# LTE_GPS.net
KiCad netlist of a schematic drawn in Altium Designer
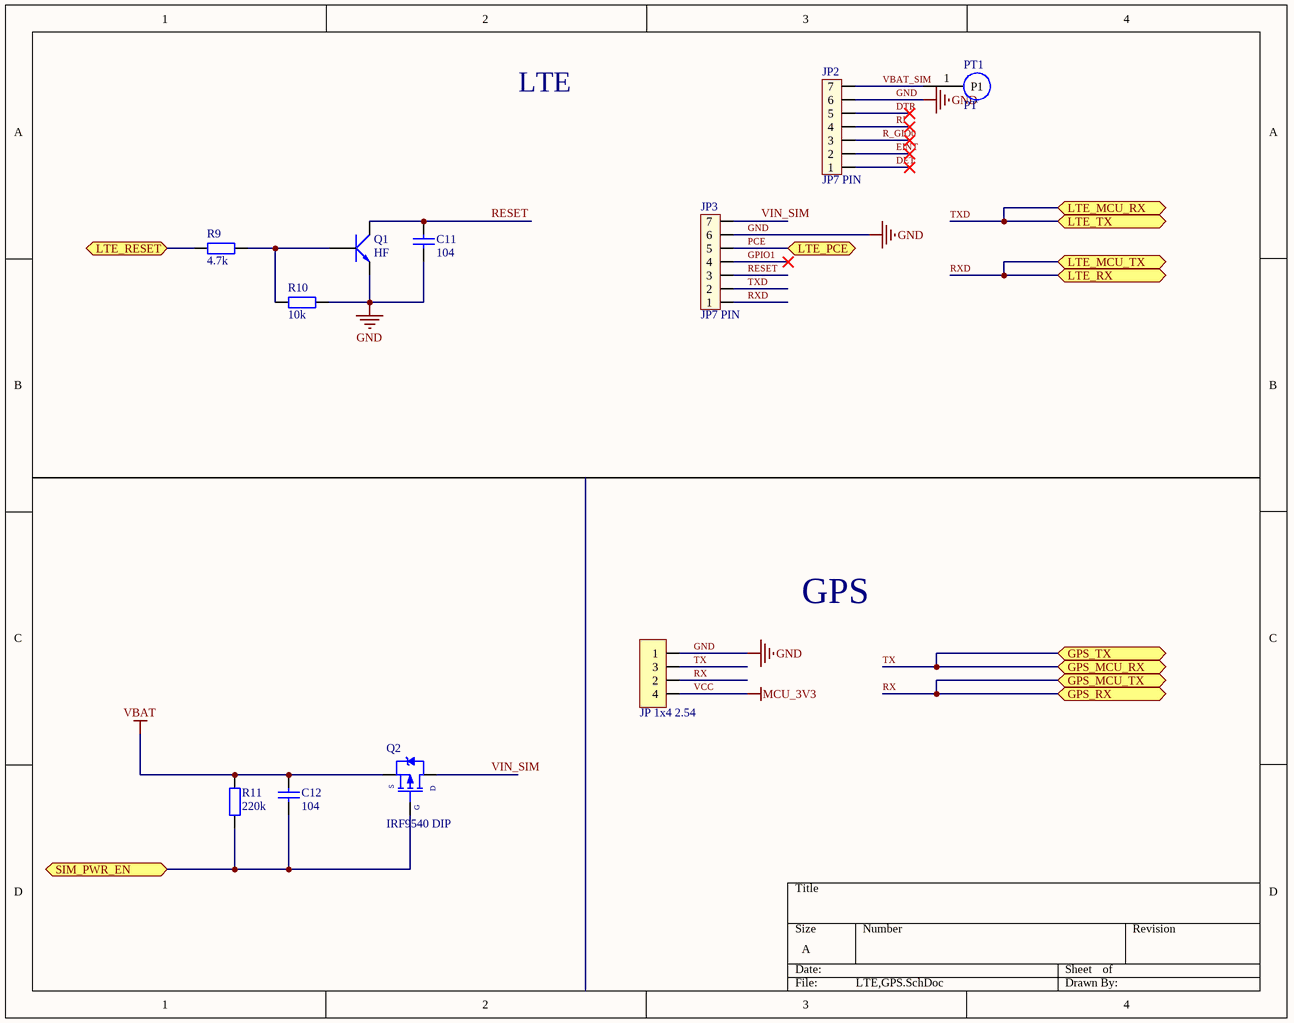
[diagram p0: LTE,GPS.SchDoc]

(export (version "E")
  (design (tool "Eeschema 10.0.6"))
  (components
    (comp (ref "C11")
      (value "104")
      (footprint "tu 0805")
      (description "Dán")
      (libsource (lib "Altium_Lib_by_KhueNguyenCreator") (part "Tu 0805 104 50V 10%"))
    )
    (comp (ref "C12")
      (value "104")
      (footprint "tu 0805")
      (description "Dán")
      (libsource (lib "Altium_Lib_by_KhueNguyenCreator") (part "Tu 0805 104 50V 10%"))
    )
    (comp (ref "JP2") (value "JP7 PIN") (footprint "JP7") (libsource (lib "syhaunguyen") (part "JP7")))
    (comp (ref "JP3") (value "JP7 PIN") (footprint "JP7") (libsource (lib "syhaunguyen") (part "JP7")))
    (comp (ref "JP4")
      (value "JP 1x4 2.54")
      (footprint "JP 1x4 DC")
      (description "Cắm")
      (libsource (lib "Altium_Lib_by_KhueNguyenCreator") (part "JP 1x4 2.54 Duc Cong"))
    )
    (comp (ref "PT1") (value "PT") (footprint "Test pont") (libsource (lib "Test pont") (part "test pont")))
    (comp (ref "Q1")
      (value "HF")
      (footprint "SOT23")
      (description "NPN transistor")
      (libsource (lib "Altium_Lib_by_KhueNguyenCreator") (part "C1815 HF SMD"))
    )
    (comp (ref "Q2")
      (value "IRF9540 DIP")
      (footprint "DPAK254P1511X469-3N")
      (description "P-Channel Power MOSFET")
      (fields (field (name "PUBLISHER") "Altium Limited"))
      (libsource (lib "Altium_Lib_by_KhueNguyenCreator") (part "IRF9540 DIP"))
    )
    (comp (ref "R9")
      (value "4.7k")
      (footprint "tro smd 0805")
      (description "Dán")
      (libsource (lib "Altium_Lib_by_KhueNguyenCreator") (part "Tro 0805 5% 4.7k"))
    )
    (comp (ref "R10")
      (value "10k")
      (footprint "tro smd 0805")
      (description "Dán")
      (libsource (lib "Altium_Lib_by_KhueNguyenCreator") (part "Tro 0805 5% 10k"))
    )
    (comp (ref "R11")
      (value "220k")
      (footprint "tro smd 0805")
      (description "Dán")
      (libsource (lib "Altium_Lib_by_KhueNguyenCreator") (part "Tro 0805 5% 220k"))
    )
  )
  (nets
    (net (code "1") (name "/DET") (class "Default")
      (node (ref "JP2") (pin "1") (pinfunction "1_1") (pintype "passive+no_connect"))
    )
    (net (code "2") (name "/DTR") (class "Default")
      (node (ref "JP2") (pin "5") (pinfunction "5_5") (pintype "passive+no_connect"))
    )
    (net (code "3") (name "/EINT") (class "Default")
      (node (ref "JP2") (pin "2") (pinfunction "2_2") (pintype "passive+no_connect"))
    )
    (net (code "4") (name "/GPIO1") (class "Default")
      (node (ref "JP3") (pin "4") (pinfunction "4_4") (pintype "passive+no_connect"))
    )
    (net (code "5") (name "/LTE_RESET") (class "Default")
      (node (ref "R9") (pin "1") (pinfunction "1_1") (pintype "passive"))
    )
    (net (code "6") (name "/PCE") (class "Default")
      (node (ref "JP3") (pin "5") (pinfunction "5_5") (pintype "passive"))
    )
    (net (code "7") (name "/RESET") (class "Default")
      (node (ref "C11") (pin "2") (pinfunction "2_2") (pintype "passive"))
      (node (ref "JP3") (pin "3") (pinfunction "3_3") (pintype "passive"))
      (node (ref "Q1") (pin "3") (pinfunction "C_3") (pintype "passive"))
    )
    (net (code "8") (name "/RI") (class "Default")
      (node (ref "JP2") (pin "4") (pinfunction "4_4") (pintype "passive+no_connect"))
    )
    (net (code "9") (name "/RX") (class "Default")
      (node (ref "JP4") (pin "2") (pinfunction "2_2") (pintype "passive"))
    )
    (net (code "10") (name "/RXD") (class "Default")
      (node (ref "JP3") (pin "1") (pinfunction "1_1") (pintype "passive"))
    )
    (net (code "11") (name "/R_GIO0") (class "Default")
      (node (ref "JP2") (pin "3") (pinfunction "3_3") (pintype "passive+no_connect"))
    )
    (net (code "12") (name "/SIM_PWR_EN") (class "Default")
      (node (ref "C12") (pin "1") (pinfunction "1_1") (pintype "passive"))
      (node (ref "Q2") (pin "1") (pinfunction "G_1") (pintype "passive"))
      (node (ref "R11") (pin "1") (pinfunction "1_1") (pintype "passive"))
    )
    (net (code "13") (name "/TX") (class "Default")
      (node (ref "JP4") (pin "3") (pinfunction "3_3") (pintype "passive"))
    )
    (net (code "14") (name "/TXD") (class "Default")
      (node (ref "JP3") (pin "2") (pinfunction "2_2") (pintype "passive"))
    )
    (net (code "15") (name "/VBAT_SIM") (class "Default")
      (node (ref "JP2") (pin "7") (pinfunction "7_7") (pintype "passive"))
      (node (ref "PT1") (pin "1") (pinfunction "P1_1") (pintype "passive"))
    )
    (net (code "16") (name "/VIN_SIM") (class "Default")
      (node (ref "JP3") (pin "7") (pinfunction "7_7") (pintype "passive"))
      (node (ref "Q2") (pin "2") (pinfunction "D_2") (pintype "passive"))
    )
    (net (code "17") (name "GND") (class "Default")
      (node (ref "C11") (pin "1") (pinfunction "1_1") (pintype "passive"))
      (node (ref "JP2") (pin "6") (pinfunction "6_6") (pintype "passive"))
      (node (ref "JP3") (pin "6") (pinfunction "6_6") (pintype "passive"))
      (node (ref "JP4") (pin "1") (pinfunction "1_1") (pintype "passive"))
      (node (ref "Q1") (pin "2") (pinfunction "E_2") (pintype "passive"))
      (node (ref "R10") (pin "2") (pinfunction "2_2") (pintype "passive"))
    )
    (net (code "18") (name "MCU_3V3") (class "Default")
      (node (ref "JP4") (pin "4") (pinfunction "4_4") (pintype "passive"))
    )
    (net (code "19") (name "Net-(Q1-B)") (class "Default")
      (node (ref "Q1") (pin "1") (pinfunction "B_1") (pintype "passive"))
      (node (ref "R10") (pin "1") (pinfunction "1_1") (pintype "passive"))
      (node (ref "R9") (pin "2") (pinfunction "2_2") (pintype "passive"))
    )
    (net (code "20") (name "VBAT") (class "Default")
      (node (ref "C12") (pin "2") (pinfunction "2_2") (pintype "passive"))
      (node (ref "Q2") (pin "3") (pinfunction "S_3") (pintype "passive"))
      (node (ref "R11") (pin "2") (pinfunction "2_2") (pintype "passive"))
    )
  )
)
